# Bpod_Controller.net
KiCad netlist of a schematic drawn in Altium Designer
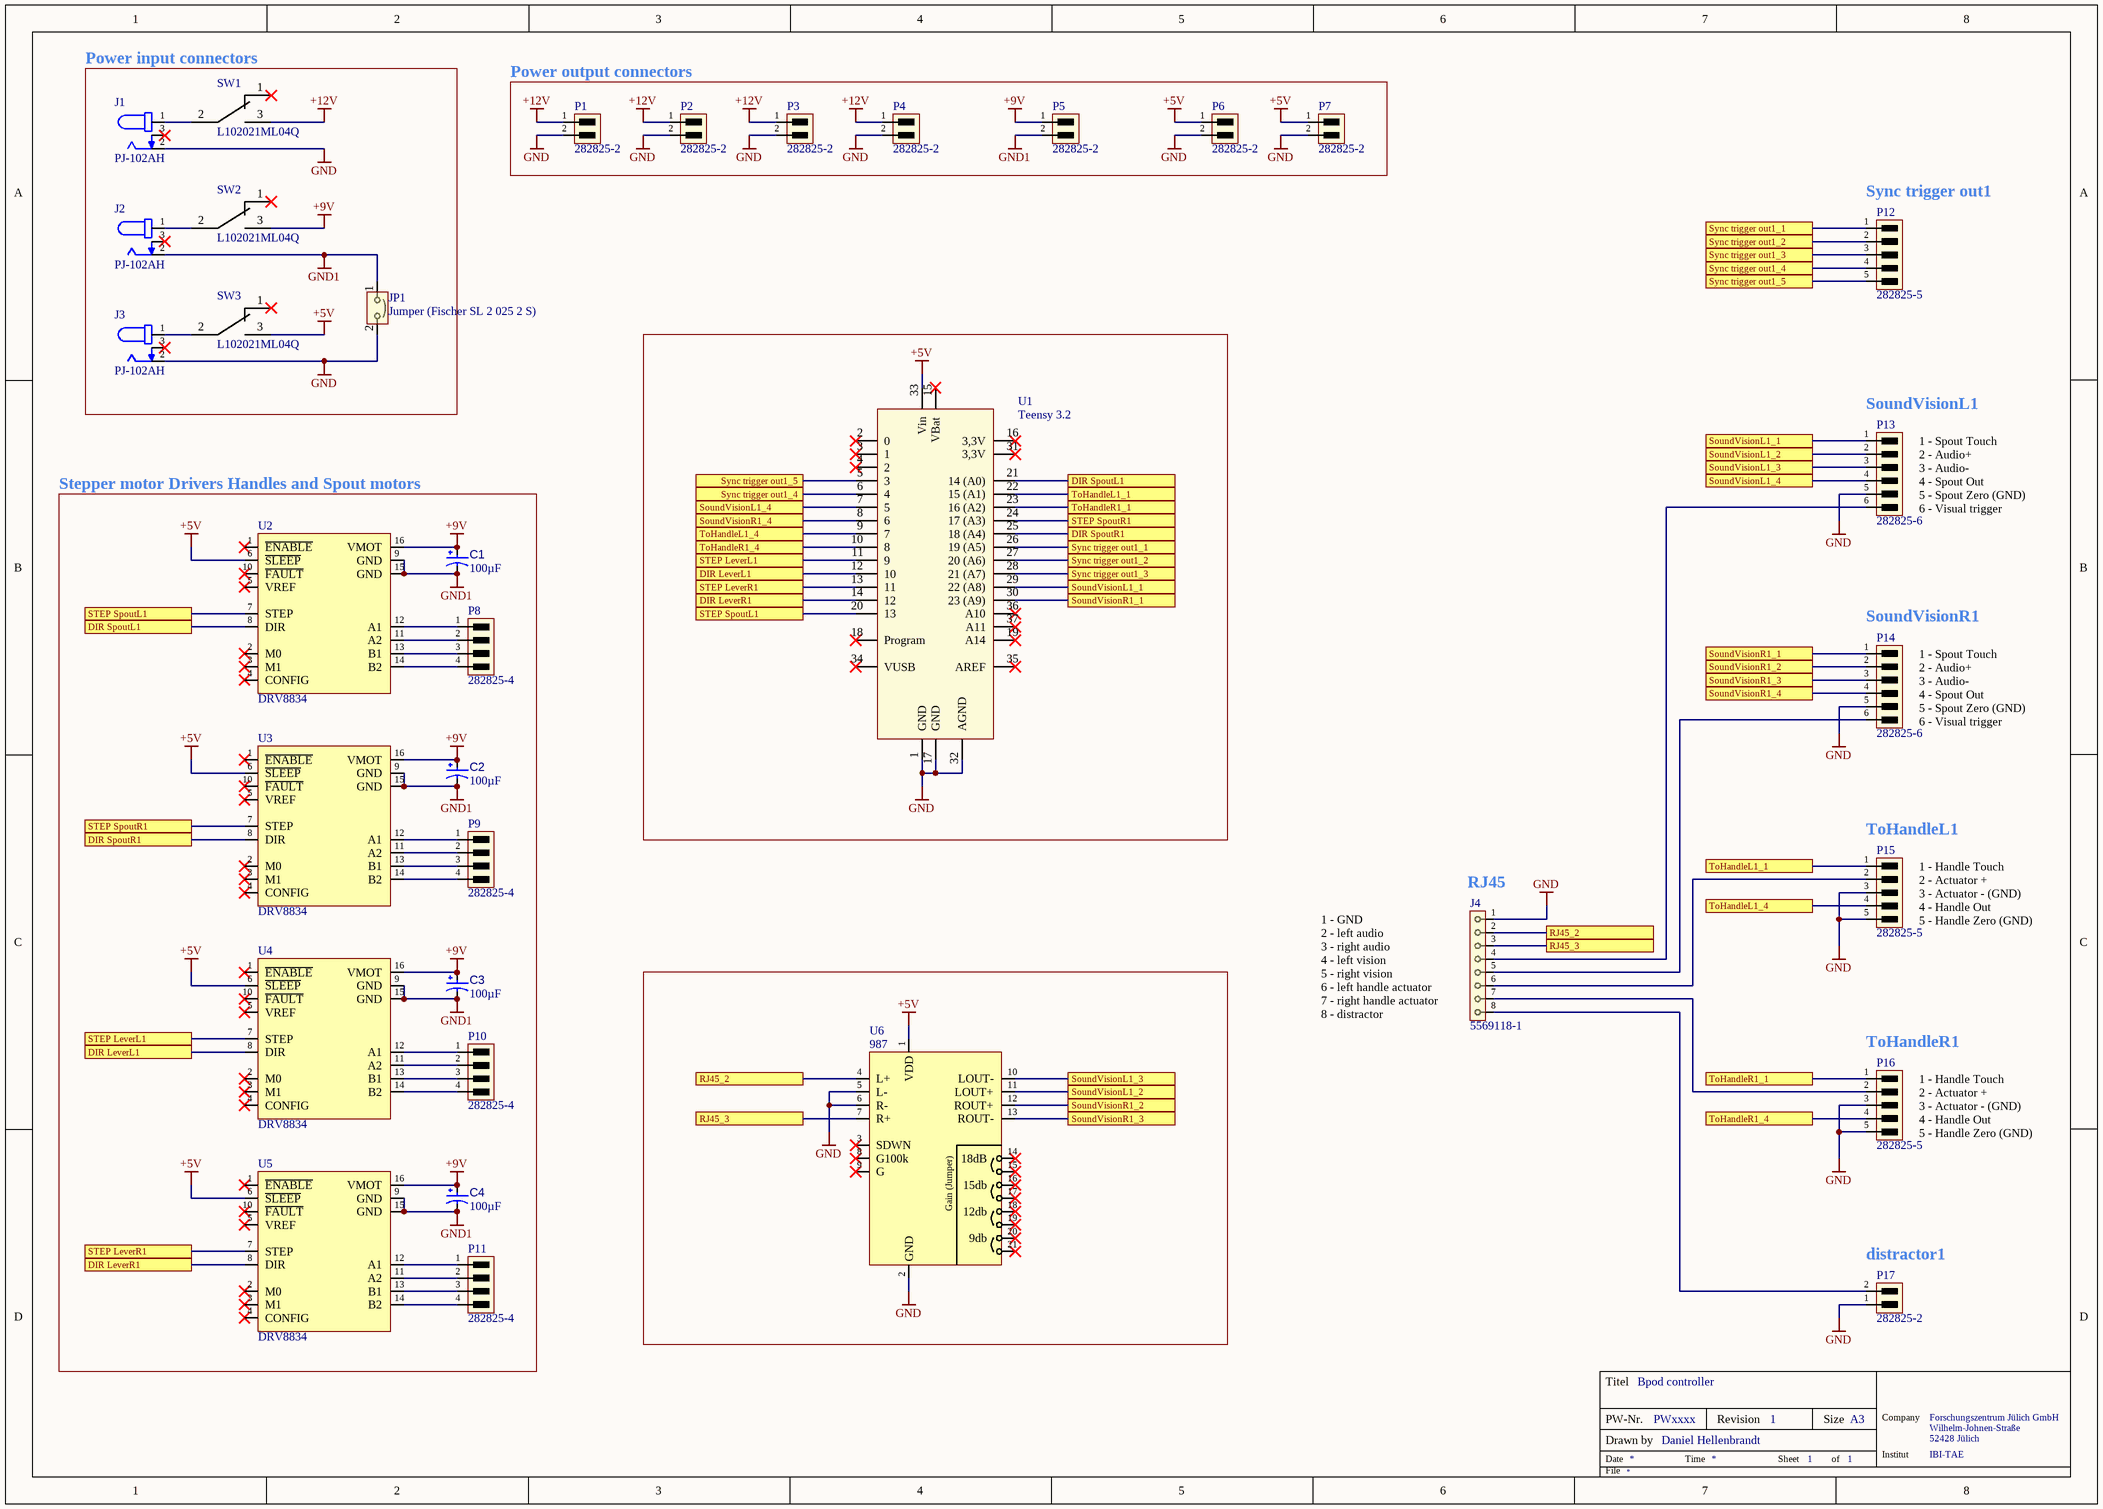
[diagram p0: Bpod Controller.SchDoc]

(export (version "E")
  (design (tool "Eeschema 10.0.6"))
  (components
    (comp (ref "C1")
      (value "100µF")
      (footprint "AVX-TAJ-C-2_M")
      (description "Standard Tantalum, 100 uF, +/- 10%, 16 V, -55 to 125 degC, 2312 (6032 Metric), RoHS, Tape and Reel")
      (fields (field (name "TOLERANCE") "10%") (field (name "MANUFACTURER") "AVX"))
      (libsource (lib "Forschungszentrum Jülich GmbH") (part "CAP-P-2"))
    )
    (comp (ref "C2")
      (value "100µF")
      (footprint "AVX-TAJ-C-2_M")
      (description "Standard Tantalum, 100 uF, +/- 10%, 16 V, -55 to 125 degC, 2312 (6032 Metric), RoHS, Tape and Reel")
      (fields (field (name "TOLERANCE") "10%") (field (name "MANUFACTURER") "AVX"))
      (libsource (lib "Forschungszentrum Jülich GmbH") (part "CAP-P-2"))
    )
    (comp (ref "C3")
      (value "100µF")
      (footprint "AVX-TAJ-C-2_M")
      (description "Standard Tantalum, 100 uF, +/- 10%, 16 V, -55 to 125 degC, 2312 (6032 Metric), RoHS, Tape and Reel")
      (fields (field (name "TOLERANCE") "10%") (field (name "MANUFACTURER") "AVX"))
      (libsource (lib "Forschungszentrum Jülich GmbH") (part "CAP-P-2"))
    )
    (comp (ref "C4")
      (value "100µF")
      (footprint "AVX-TAJ-C-2_M")
      (description "Standard Tantalum, 100 uF, +/- 10%, 16 V, -55 to 125 degC, 2312 (6032 Metric), RoHS, Tape and Reel")
      (fields (field (name "TOLERANCE") "10%") (field (name "MANUFACTURER") "AVX"))
      (libsource (lib "Forschungszentrum Jülich GmbH") (part "CAP-P-2"))
    )
    (comp (ref "J1")
      (value "PJ-102AH")
      (footprint "CUI_PJ-102AH")
      (description "12V, 2.5A, 2mm Dia")
      (fields (field (name "USER") "IBI-TAE"))
      (libsource (lib "Forschungszentrum Jülich GmbH") (part "PJ-102AH"))
    )
    (comp (ref "J2")
      (value "PJ-102AH")
      (footprint "CUI_PJ-102AH")
      (description "12V, 2.5A, 2mm Dia")
      (fields (field (name "USER") "IBI-TAE"))
      (libsource (lib "Forschungszentrum Jülich GmbH") (part "PJ-102AH"))
    )
    (comp (ref "J3")
      (value "PJ-102AH")
      (footprint "CUI_PJ-102AH")
      (description "12V, 2.5A, 2mm Dia")
      (fields (field (name "USER") "IBI-TAE"))
      (libsource (lib "Forschungszentrum Jülich GmbH") (part "PJ-102AH"))
    )
    (comp (ref "J4")
      (value "5569118-1")
      (footprint "5569118-1-Footprint-1")
      (description "Telecom and Datacom Connector, 8 Contact(s), Female, Right Angle, Solder Terminal, Locking, Jack")
      (fields (field (name "USER") "IBI-TAE"))
      (libsource (lib "Forschungszentrum Jülich GmbH") (part "5569118-1"))
    )
    (comp (ref "JP1")
      (value "Jumper (Fischer SL 2 025 2 S)")
      (footprint "SL 2_025_ 72_S-Footprint-1")
      (description "Fischer Elektronik SL 2/025/ 72/S")
      (fields (field (name "USER") "IBI-TAE"))
      (libsource (lib "Forschungszentrum Jülich GmbH") (part "SL 2_025_ 2_S"))
    )
    (comp (ref "P1")
      (value "282825-2")
      (footprint "282825-4-Footprint-1")
      (description "Strip Terminal Block, 15A, 1 Row(s), 1 Deck(s)")
      (fields (field (name "USER") "IBI-TAE"))
      (libsource (lib "Forschungszentrum Jülich GmbH") (part "282825-2"))
    )
    (comp (ref "P2")
      (value "282825-2")
      (footprint "282825-4-Footprint-1")
      (description "Strip Terminal Block, 15A, 1 Row(s), 1 Deck(s)")
      (fields (field (name "USER") "IBI-TAE"))
      (libsource (lib "Forschungszentrum Jülich GmbH") (part "282825-2"))
    )
    (comp (ref "P3")
      (value "282825-2")
      (footprint "282825-4-Footprint-1")
      (description "Strip Terminal Block, 15A, 1 Row(s), 1 Deck(s)")
      (fields (field (name "USER") "IBI-TAE"))
      (libsource (lib "Forschungszentrum Jülich GmbH") (part "282825-2"))
    )
    (comp (ref "P4")
      (value "282825-2")
      (footprint "282825-4-Footprint-1")
      (description "Strip Terminal Block, 15A, 1 Row(s), 1 Deck(s)")
      (fields (field (name "USER") "IBI-TAE"))
      (libsource (lib "Forschungszentrum Jülich GmbH") (part "282825-2"))
    )
    (comp (ref "P5")
      (value "282825-2")
      (footprint "282825-4-Footprint-1")
      (description "Strip Terminal Block, 15A, 1 Row(s), 1 Deck(s)")
      (fields (field (name "USER") "IBI-TAE"))
      (libsource (lib "Forschungszentrum Jülich GmbH") (part "282825-2"))
    )
    (comp (ref "P6")
      (value "282825-2")
      (footprint "282825-4-Footprint-1")
      (description "Strip Terminal Block, 15A, 1 Row(s), 1 Deck(s)")
      (fields (field (name "USER") "IBI-TAE"))
      (libsource (lib "Forschungszentrum Jülich GmbH") (part "282825-2"))
    )
    (comp (ref "P7")
      (value "282825-2")
      (footprint "282825-4-Footprint-1")
      (description "Strip Terminal Block, 15A, 1 Row(s), 1 Deck(s)")
      (fields (field (name "USER") "IBI-TAE"))
      (libsource (lib "Forschungszentrum Jülich GmbH") (part "282825-2"))
    )
    (comp (ref "P8")
      (value "282825-4")
      (footprint "282825-4-Footprint-1")
      (description "Strip Terminal Block, 15A, 1 Row(s), 1 Deck(s)")
      (fields (field (name "USER") "IBI-TAE"))
      (libsource (lib "Forschungszentrum Jülich GmbH") (part "282825-4"))
    )
    (comp (ref "P9")
      (value "282825-4")
      (footprint "282825-4-Footprint-1")
      (description "Strip Terminal Block, 15A, 1 Row(s), 1 Deck(s)")
      (fields (field (name "USER") "IBI-TAE"))
      (libsource (lib "Forschungszentrum Jülich GmbH") (part "282825-4"))
    )
    (comp (ref "P10")
      (value "282825-4")
      (footprint "282825-4-Footprint-1")
      (description "Strip Terminal Block, 15A, 1 Row(s), 1 Deck(s)")
      (fields (field (name "USER") "IBI-TAE"))
      (libsource (lib "Forschungszentrum Jülich GmbH") (part "282825-4"))
    )
    (comp (ref "P11")
      (value "282825-4")
      (footprint "282825-4-Footprint-1")
      (description "Strip Terminal Block, 15A, 1 Row(s), 1 Deck(s)")
      (fields (field (name "USER") "IBI-TAE"))
      (libsource (lib "Forschungszentrum Jülich GmbH") (part "282825-4"))
    )
    (comp (ref "P12")
      (value "282825-5")
      (footprint "282825-4-Footprint-1")
      (description "Strip Terminal Block, 15A, 1 Row(s), 1 Deck(s)")
      (fields (field (name "USER") "IBI-TAE"))
      (libsource (lib "Forschungszentrum Jülich GmbH") (part "282825-5"))
    )
    (comp (ref "P13")
      (value "282825-6")
      (footprint "282825-4-Footprint-1")
      (description "Strip Terminal Block, 15A, 1 Row(s), 1 Deck(s)")
      (fields (field (name "USER") "IBI-TAE"))
      (libsource (lib "Forschungszentrum Jülich GmbH") (part "282825-6"))
    )
    (comp (ref "P14")
      (value "282825-6")
      (footprint "282825-4-Footprint-1")
      (description "Strip Terminal Block, 15A, 1 Row(s), 1 Deck(s)")
      (fields (field (name "USER") "IBI-TAE"))
      (libsource (lib "Forschungszentrum Jülich GmbH") (part "282825-6"))
    )
    (comp (ref "P15")
      (value "282825-5")
      (footprint "282825-4-Footprint-1")
      (description "Strip Terminal Block, 15A, 1 Row(s), 1 Deck(s)")
      (fields (field (name "USER") "IBI-TAE"))
      (libsource (lib "Forschungszentrum Jülich GmbH") (part "282825-5"))
    )
    (comp (ref "P16")
      (value "282825-5")
      (footprint "282825-4-Footprint-1")
      (description "Strip Terminal Block, 15A, 1 Row(s), 1 Deck(s)")
      (fields (field (name "USER") "IBI-TAE"))
      (libsource (lib "Forschungszentrum Jülich GmbH") (part "282825-5"))
    )
    (comp (ref "P17")
      (value "282825-2")
      (footprint "282825-4-Footprint-1")
      (description "Strip Terminal Block, 15A, 1 Row(s), 1 Deck(s)")
      (fields (field (name "USER") "IBI-TAE"))
      (libsource (lib "") (part "282825-2_1"))
    )
    (comp (ref "SW1")
      (value "L102021ML04Q")
      (footprint "L102021ML04Q-Footprint-1")
      (description "Slide Switch, 1 Positions, SPDT, Latched, 4A, 28VDC, Solder Terminal, Through Hole-right Angle")
      (libsource (lib "Forschungszentrum Jülich GmbH") (part "L102021ML04Q-Symbol-1"))
    )
    (comp (ref "SW2")
      (value "L102021ML04Q")
      (footprint "L102021ML04Q-Footprint-1")
      (description "Slide Switch, 1 Positions, SPDT, Latched, 4A, 28VDC, Solder Terminal, Through Hole-right Angle")
      (libsource (lib "Forschungszentrum Jülich GmbH") (part "L102021ML04Q-Symbol-1"))
    )
    (comp (ref "SW3")
      (value "L102021ML04Q")
      (footprint "L102021ML04Q-Footprint-1")
      (description "Slide Switch, 1 Positions, SPDT, Latched, 4A, 28VDC, Solder Terminal, Through Hole-right Angle")
      (libsource (lib "Forschungszentrum Jülich GmbH") (part "L102021ML04Q-Symbol-1"))
    )
    (comp (ref "U1")
      (value "Teensy 3.2")
      (footprint "New footprint 1")
      (description "Development Boards & Kits, ARM Teensy 3.2 and header")
      (fields (field (name "USER") "IBI-TAE"))
      (libsource (lib "Forschungszentrum Jülich GmbH") (part "Teensy 3,2"))
    )
    (comp (ref "U2")
      (value "DRV8834")
      (footprint "DRV8825 STEPPER MOTOR DRIVER CARRIER-Footprint-1")
      (description "DRV8834 Low-Voltage Stepper Motor Driver Carrier")
      (fields (field (name "USER") "IBI-TAE"))
      (libsource (lib "Forschungszentrum Jülich GmbH") (part "Pololu DRV8834"))
    )
    (comp (ref "U3")
      (value "DRV8834")
      (footprint "DRV8825 STEPPER MOTOR DRIVER CARRIER-Footprint-1")
      (description "DRV8834 Low-Voltage Stepper Motor Driver Carrier")
      (fields (field (name "USER") "IBI-TAE"))
      (libsource (lib "Forschungszentrum Jülich GmbH") (part "Pololu DRV8834"))
    )
    (comp (ref "U4")
      (value "DRV8834")
      (footprint "DRV8825 STEPPER MOTOR DRIVER CARRIER-Footprint-1")
      (description "DRV8834 Low-Voltage Stepper Motor Driver Carrier")
      (fields (field (name "USER") "IBI-TAE"))
      (libsource (lib "Forschungszentrum Jülich GmbH") (part "Pololu DRV8834"))
    )
    (comp (ref "U5")
      (value "DRV8834")
      (footprint "DRV8825 STEPPER MOTOR DRIVER CARRIER-Footprint-1")
      (description "DRV8834 Low-Voltage Stepper Motor Driver Carrier")
      (fields (field (name "USER") "IBI-TAE"))
      (libsource (lib "Forschungszentrum Jülich GmbH") (part "Pololu DRV8834"))
    )
    (comp (ref "U6")
      (value "987")
      (footprint "987-Footprint-1")
      (description "Stereo 3.7W Class D Amplifier - Max98306; Product Range: -; Plug Type: - Rohs Compliant: Yes")
      (fields (field (name "USER") "IBI-TAE"))
      (libsource (lib "Forschungszentrum Jülich GmbH") (part "987"))
    )
  )
  (nets
    (net (code "1") (name "+5V") (class "Default")
      (node (ref "P6") (pin "1") (pinfunction "1_1") (pintype "passive"))
      (node (ref "P7") (pin "1") (pinfunction "1_1") (pintype "passive"))
      (node (ref "SW3") (pin "3") (pinfunction "3_3") (pintype "passive"))
      (node (ref "U1") (pin "33") (pinfunction "Vin_33") (pintype "power_in"))
      (node (ref "U2") (pin "6") (pinfunction "~{SLEEP}_6") (pintype "passive"))
      (node (ref "U3") (pin "6") (pinfunction "~{SLEEP}_6") (pintype "passive"))
      (node (ref "U4") (pin "6") (pinfunction "~{SLEEP}_6") (pintype "passive"))
      (node (ref "U5") (pin "6") (pinfunction "~{SLEEP}_6") (pintype "passive"))
      (node (ref "U6") (pin "1") (pinfunction "VDD_1") (pintype "passive"))
    )
    (net (code "2") (name "+9V") (class "Default")
      (node (ref "C1") (pin "1") (pinfunction "1_1") (pintype "passive"))
      (node (ref "C2") (pin "1") (pinfunction "1_1") (pintype "passive"))
      (node (ref "C3") (pin "1") (pinfunction "1_1") (pintype "passive"))
      (node (ref "C4") (pin "1") (pinfunction "1_1") (pintype "passive"))
      (node (ref "P5") (pin "1") (pinfunction "1_1") (pintype "passive"))
      (node (ref "SW2") (pin "3") (pinfunction "3_3") (pintype "passive"))
      (node (ref "U2") (pin "16") (pinfunction "VMOT_16") (pintype "passive"))
      (node (ref "U3") (pin "16") (pinfunction "VMOT_16") (pintype "passive"))
      (node (ref "U4") (pin "16") (pinfunction "VMOT_16") (pintype "passive"))
      (node (ref "U5") (pin "16") (pinfunction "VMOT_16") (pintype "passive"))
    )
    (net (code "3") (name "+12V") (class "Default")
      (node (ref "P1") (pin "1") (pinfunction "1_1") (pintype "passive"))
      (node (ref "P2") (pin "1") (pinfunction "1_1") (pintype "passive"))
      (node (ref "P3") (pin "1") (pinfunction "1_1") (pintype "passive"))
      (node (ref "P4") (pin "1") (pinfunction "1_1") (pintype "passive"))
      (node (ref "SW1") (pin "3") (pinfunction "3_3") (pintype "passive"))
    )
    (net (code "4") (name "/DIR LeverL1") (class "Default")
      (node (ref "U1") (pin "12") (pinfunction "10_12") (pintype "passive"))
      (node (ref "U4") (pin "8") (pinfunction "DIR_8") (pintype "passive"))
    )
    (net (code "5") (name "/DIR LeverR1") (class "Default")
      (node (ref "U1") (pin "14") (pinfunction "12_14") (pintype "passive"))
      (node (ref "U5") (pin "8") (pinfunction "DIR_8") (pintype "passive"))
    )
    (net (code "6") (name "/DIR SpoutL1") (class "Default")
      (node (ref "U1") (pin "21") (pinfunction "14_(A0)_21") (pintype "passive"))
      (node (ref "U2") (pin "8") (pinfunction "DIR_8") (pintype "passive"))
    )
    (net (code "7") (name "/DIR SpoutR1") (class "Default")
      (node (ref "U1") (pin "25") (pinfunction "18_(A4)_25") (pintype "passive"))
      (node (ref "U3") (pin "8") (pinfunction "DIR_8") (pintype "passive"))
    )
    (net (code "8") (name "/RJ45_2") (class "Default")
      (node (ref "J4") (pin "2") (pinfunction "2_2") (pintype "passive"))
      (node (ref "U6") (pin "4") (pinfunction "L+_4") (pintype "passive"))
    )
    (net (code "9") (name "/RJ45_3") (class "Default")
      (node (ref "J4") (pin "3") (pinfunction "3_3") (pintype "passive"))
      (node (ref "U6") (pin "7") (pinfunction "R+_7") (pintype "passive"))
    )
    (net (code "10") (name "/STEP LeverL1") (class "Default")
      (node (ref "U1") (pin "11") (pinfunction "9_11") (pintype "passive"))
      (node (ref "U4") (pin "7") (pinfunction "STEP_7") (pintype "passive"))
    )
    (net (code "11") (name "/STEP LeverR1") (class "Default")
      (node (ref "U1") (pin "13") (pinfunction "11_13") (pintype "passive"))
      (node (ref "U5") (pin "7") (pinfunction "STEP_7") (pintype "passive"))
    )
    (net (code "12") (name "/STEP SpoutL1") (class "Default")
      (node (ref "U1") (pin "20") (pinfunction "13_20") (pintype "passive"))
      (node (ref "U2") (pin "7") (pinfunction "STEP_7") (pintype "passive"))
    )
    (net (code "13") (name "/STEP SpoutR1") (class "Default")
      (node (ref "U1") (pin "24") (pinfunction "17_(A3)_24") (pintype "passive"))
      (node (ref "U3") (pin "7") (pinfunction "STEP_7") (pintype "passive"))
    )
    (net (code "14") (name "/SoundVisionL1_1") (class "Default")
      (node (ref "P13") (pin "1") (pinfunction "1_1") (pintype "passive"))
      (node (ref "U1") (pin "29") (pinfunction "22_(A8)_29") (pintype "passive"))
    )
    (net (code "15") (name "/SoundVisionL1_2") (class "Default")
      (node (ref "P13") (pin "2") (pinfunction "2_2") (pintype "passive"))
      (node (ref "U6") (pin "11") (pinfunction "LOUT+_11") (pintype "passive"))
    )
    (net (code "16") (name "/SoundVisionL1_3") (class "Default")
      (node (ref "P13") (pin "3") (pinfunction "3_3") (pintype "passive"))
      (node (ref "U6") (pin "10") (pinfunction "LOUT-_10") (pintype "passive"))
    )
    (net (code "17") (name "/SoundVisionL1_4") (class "Default")
      (node (ref "P13") (pin "4") (pinfunction "4_4") (pintype "passive"))
      (node (ref "U1") (pin "7") (pinfunction "5_7") (pintype "passive"))
    )
    (net (code "18") (name "/SoundVisionR1_1") (class "Default")
      (node (ref "P14") (pin "1") (pinfunction "1_1") (pintype "passive"))
      (node (ref "U1") (pin "30") (pinfunction "23_(A9)_30") (pintype "passive"))
    )
    (net (code "19") (name "/SoundVisionR1_2") (class "Default")
      (node (ref "P14") (pin "2") (pinfunction "2_2") (pintype "passive"))
      (node (ref "U6") (pin "12") (pinfunction "ROUT+_12") (pintype "passive"))
    )
    (net (code "20") (name "/SoundVisionR1_3") (class "Default")
      (node (ref "P14") (pin "3") (pinfunction "3_3") (pintype "passive"))
      (node (ref "U6") (pin "13") (pinfunction "ROUT-_13") (pintype "passive"))
    )
    (net (code "21") (name "/SoundVisionR1_4") (class "Default")
      (node (ref "P14") (pin "4") (pinfunction "4_4") (pintype "passive"))
      (node (ref "U1") (pin "8") (pinfunction "6_8") (pintype "passive"))
    )
    (net (code "22") (name "/Sync trigger out1_1") (class "Default")
      (node (ref "P12") (pin "1") (pinfunction "1_1") (pintype "passive"))
      (node (ref "U1") (pin "26") (pinfunction "19_(A5)_26") (pintype "passive"))
    )
    (net (code "23") (name "/Sync trigger out1_2") (class "Default")
      (node (ref "P12") (pin "2") (pinfunction "2_2") (pintype "passive"))
      (node (ref "U1") (pin "27") (pinfunction "20_(A6)_27") (pintype "passive"))
    )
    (net (code "24") (name "/Sync trigger out1_3") (class "Default")
      (node (ref "P12") (pin "3") (pinfunction "3_3") (pintype "passive"))
      (node (ref "U1") (pin "28") (pinfunction "21_(A7)_28") (pintype "passive"))
    )
    (net (code "25") (name "/Sync trigger out1_4") (class "Default")
      (node (ref "P12") (pin "4") (pinfunction "4_4") (pintype "passive"))
      (node (ref "U1") (pin "6") (pinfunction "4_6") (pintype "passive"))
    )
    (net (code "26") (name "/Sync trigger out1_5") (class "Default")
      (node (ref "P12") (pin "5") (pinfunction "5_5") (pintype "passive"))
      (node (ref "U1") (pin "5") (pinfunction "3_5") (pintype "passive"))
    )
    (net (code "27") (name "/ToHandleL1_1") (class "Default")
      (node (ref "P15") (pin "1") (pinfunction "1_1") (pintype "passive"))
      (node (ref "U1") (pin "22") (pinfunction "15_(A1)_22") (pintype "passive"))
    )
    (net (code "28") (name "/ToHandleL1_4") (class "Default")
      (node (ref "P15") (pin "4") (pinfunction "4_4") (pintype "passive"))
      (node (ref "U1") (pin "9") (pinfunction "7_9") (pintype "passive"))
    )
    (net (code "29") (name "/ToHandleR1_1") (class "Default")
      (node (ref "P16") (pin "1") (pinfunction "1_1") (pintype "passive"))
      (node (ref "U1") (pin "23") (pinfunction "16_(A2)_23") (pintype "passive"))
    )
    (net (code "30") (name "/ToHandleR1_4") (class "Default")
      (node (ref "P16") (pin "4") (pinfunction "4_4") (pintype "passive"))
      (node (ref "U1") (pin "10") (pinfunction "8_10") (pintype "passive"))
    )
    (net (code "31") (name "GND") (class "Default")
      (node (ref "J1") (pin "2") (pinfunction "2_2") (pintype "passive"))
      (node (ref "J3") (pin "2") (pinfunction "2_2") (pintype "passive"))
      (node (ref "J4") (pin "1") (pinfunction "1_1") (pintype "passive"))
      (node (ref "JP1") (pin "2") (pinfunction "2_2") (pintype "passive"))
      (node (ref "P1") (pin "2") (pinfunction "2_2") (pintype "passive"))
      (node (ref "P13") (pin "5") (pinfunction "5_5") (pintype "passive"))
      (node (ref "P14") (pin "5") (pinfunction "5_5") (pintype "passive"))
      (node (ref "P15") (pin "3") (pinfunction "3_3") (pintype "passive"))
      (node (ref "P15") (pin "5") (pinfunction "5_5") (pintype "passive"))
      (node (ref "P16") (pin "3") (pinfunction "3_3") (pintype "passive"))
      (node (ref "P16") (pin "5") (pinfunction "5_5") (pintype "passive"))
      (node (ref "P17") (pin "1") (pinfunction "1_1") (pintype "passive"))
      (node (ref "P2") (pin "2") (pinfunction "2_2") (pintype "passive"))
      (node (ref "P3") (pin "2") (pinfunction "2_2") (pintype "passive"))
      (node (ref "P4") (pin "2") (pinfunction "2_2") (pintype "passive"))
      (node (ref "P6") (pin "2") (pinfunction "2_2") (pintype "passive"))
      (node (ref "P7") (pin "2") (pinfunction "2_2") (pintype "passive"))
      (node (ref "U1") (pin "1") (pinfunction "GND_1") (pintype "passive"))
      (node (ref "U1") (pin "17") (pinfunction "GND_17") (pintype "passive"))
      (node (ref "U1") (pin "32") (pinfunction "AGND_32") (pintype "passive"))
      (node (ref "U6") (pin "2") (pinfunction "GND_2") (pintype "passive"))
      (node (ref "U6") (pin "5") (pinfunction "L-_5") (pintype "passive"))
      (node (ref "U6") (pin "6") (pinfunction "R-_6") (pintype "passive"))
    )
    (net (code "32") (name "GND1") (class "Default")
      (node (ref "C1") (pin "2") (pinfunction "2_2") (pintype "passive"))
      (node (ref "C2") (pin "2") (pinfunction "2_2") (pintype "passive"))
      (node (ref "C3") (pin "2") (pinfunction "2_2") (pintype "passive"))
      (node (ref "C4") (pin "2") (pinfunction "2_2") (pintype "passive"))
      (node (ref "J2") (pin "2") (pinfunction "2_2") (pintype "passive"))
      (node (ref "JP1") (pin "1") (pinfunction "1_1") (pintype "passive"))
      (node (ref "P5") (pin "2") (pinfunction "2_2") (pintype "passive"))
      (node (ref "U2") (pin "15") (pinfunction "GND_15") (pintype "passive"))
      (node (ref "U2") (pin "9") (pinfunction "GND_9") (pintype "passive"))
      (node (ref "U3") (pin "15") (pinfunction "GND_15") (pintype "passive"))
      (node (ref "U3") (pin "9") (pinfunction "GND_9") (pintype "passive"))
      (node (ref "U4") (pin "15") (pinfunction "GND_15") (pintype "passive"))
      (node (ref "U4") (pin "9") (pinfunction "GND_9") (pintype "passive"))
      (node (ref "U5") (pin "15") (pinfunction "GND_15") (pintype "passive"))
      (node (ref "U5") (pin "9") (pinfunction "GND_9") (pintype "passive"))
    )
    (net (code "33") (name "Net-(J1-Pad1)") (class "Default")
      (node (ref "J1") (pin "1") (pinfunction "1_1") (pintype "passive"))
      (node (ref "SW1") (pin "2") (pinfunction "2_2") (pintype "passive"))
    )
    (net (code "34") (name "Net-(J2-Pad1)") (class "Default")
      (node (ref "J2") (pin "1") (pinfunction "1_1") (pintype "passive"))
      (node (ref "SW2") (pin "2") (pinfunction "2_2") (pintype "passive"))
    )
    (net (code "35") (name "Net-(J3-Pad1)") (class "Default")
      (node (ref "J3") (pin "1") (pinfunction "1_1") (pintype "passive"))
      (node (ref "SW3") (pin "2") (pinfunction "2_2") (pintype "passive"))
    )
    (net (code "36") (name "Net-(J4-Pad4)") (class "Default")
      (node (ref "J4") (pin "4") (pinfunction "4_4") (pintype "passive"))
      (node (ref "P13") (pin "6") (pinfunction "6_6") (pintype "passive"))
    )
    (net (code "37") (name "Net-(J4-Pad5)") (class "Default")
      (node (ref "J4") (pin "5") (pinfunction "5_5") (pintype "passive"))
      (node (ref "P14") (pin "6") (pinfunction "6_6") (pintype "passive"))
    )
    (net (code "38") (name "Net-(J4-Pad6)") (class "Default")
      (node (ref "J4") (pin "6") (pinfunction "6_6") (pintype "passive"))
      (node (ref "P15") (pin "2") (pinfunction "2_2") (pintype "passive"))
    )
    (net (code "39") (name "Net-(J4-Pad7)") (class "Default")
      (node (ref "J4") (pin "7") (pinfunction "7_7") (pintype "passive"))
      (node (ref "P16") (pin "2") (pinfunction "2_2") (pintype "passive"))
    )
    (net (code "40") (name "Net-(J4-Pad8)") (class "Default")
      (node (ref "J4") (pin "8") (pinfunction "8_8") (pintype "passive"))
      (node (ref "P17") (pin "2") (pinfunction "2_2") (pintype "passive"))
    )
    (net (code "41") (name "Net-(U2-A1)") (class "Default")
      (node (ref "P8") (pin "1") (pinfunction "1_1") (pintype "passive"))
      (node (ref "U2") (pin "12") (pinfunction "A1_12") (pintype "passive"))
    )
    (net (code "42") (name "Net-(U2-A2)") (class "Default")
      (node (ref "P8") (pin "2") (pinfunction "2_2") (pintype "passive"))
      (node (ref "U2") (pin "11") (pinfunction "A2_11") (pintype "passive"))
    )
    (net (code "43") (name "Net-(U2-B1)") (class "Default")
      (node (ref "P8") (pin "3") (pinfunction "3_3") (pintype "passive"))
      (node (ref "U2") (pin "13") (pinfunction "B1_13") (pintype "passive"))
    )
    (net (code "44") (name "Net-(U2-B2)") (class "Default")
      (node (ref "P8") (pin "4") (pinfunction "4_4") (pintype "passive"))
      (node (ref "U2") (pin "14") (pinfunction "B2_14") (pintype "passive"))
    )
    (net (code "45") (name "Net-(U3-A1)") (class "Default")
      (node (ref "P9") (pin "1") (pinfunction "1_1") (pintype "passive"))
      (node (ref "U3") (pin "12") (pinfunction "A1_12") (pintype "passive"))
    )
    (net (code "46") (name "Net-(U3-A2)") (class "Default")
      (node (ref "P9") (pin "2") (pinfunction "2_2") (pintype "passive"))
      (node (ref "U3") (pin "11") (pinfunction "A2_11") (pintype "passive"))
    )
    (net (code "47") (name "Net-(U3-B1)") (class "Default")
      (node (ref "P9") (pin "3") (pinfunction "3_3") (pintype "passive"))
      (node (ref "U3") (pin "13") (pinfunction "B1_13") (pintype "passive"))
    )
    (net (code "48") (name "Net-(U3-B2)") (class "Default")
      (node (ref "P9") (pin "4") (pinfunction "4_4") (pintype "passive"))
      (node (ref "U3") (pin "14") (pinfunction "B2_14") (pintype "passive"))
    )
    (net (code "49") (name "Net-(U4-A1)") (class "Default")
      (node (ref "P10") (pin "1") (pinfunction "1_1") (pintype "passive"))
      (node (ref "U4") (pin "12") (pinfunction "A1_12") (pintype "passive"))
    )
    (net (code "50") (name "Net-(U4-A2)") (class "Default")
      (node (ref "P10") (pin "2") (pinfunction "2_2") (pintype "passive"))
      (node (ref "U4") (pin "11") (pinfunction "A2_11") (pintype "passive"))
    )
    (net (code "51") (name "Net-(U4-B1)") (class "Default")
      (node (ref "P10") (pin "3") (pinfunction "3_3") (pintype "passive"))
      (node (ref "U4") (pin "13") (pinfunction "B1_13") (pintype "passive"))
    )
    (net (code "52") (name "Net-(U4-B2)") (class "Default")
      (node (ref "P10") (pin "4") (pinfunction "4_4") (pintype "passive"))
      (node (ref "U4") (pin "14") (pinfunction "B2_14") (pintype "passive"))
    )
    (net (code "53") (name "Net-(U5-A1)") (class "Default")
      (node (ref "P11") (pin "1") (pinfunction "1_1") (pintype "passive"))
      (node (ref "U5") (pin "12") (pinfunction "A1_12") (pintype "passive"))
    )
    (net (code "54") (name "Net-(U5-A2)") (class "Default")
      (node (ref "P11") (pin "2") (pinfunction "2_2") (pintype "passive"))
      (node (ref "U5") (pin "11") (pinfunction "A2_11") (pintype "passive"))
    )
    (net (code "55") (name "Net-(U5-B1)") (class "Default")
      (node (ref "P11") (pin "3") (pinfunction "3_3") (pintype "passive"))
      (node (ref "U5") (pin "13") (pinfunction "B1_13") (pintype "passive"))
    )
    (net (code "56") (name "Net-(U5-B2)") (class "Default")
      (node (ref "P11") (pin "4") (pinfunction "4_4") (pintype "passive"))
      (node (ref "U5") (pin "14") (pinfunction "B2_14") (pintype "passive"))
    )
    (net (code "57") (name "unconnected-(J1-Pad3)") (class "Default")
      (node (ref "J1") (pin "3") (pinfunction "3_3") (pintype "passive"))
    )
    (net (code "58") (name "unconnected-(J2-Pad3)") (class "Default")
      (node (ref "J2") (pin "3") (pinfunction "3_3") (pintype "passive+no_connect"))
    )
    (net (code "59") (name "unconnected-(J3-Pad3)") (class "Default")
      (node (ref "J3") (pin "3") (pinfunction "3_3") (pintype "passive+no_connect"))
    )
    (net (code "60") (name "unconnected-(SW1-Pad1)") (class "Default")
      (node (ref "SW1") (pin "1") (pinfunction "1_1") (pintype "passive+no_connect"))
    )
    (net (code "61") (name "unconnected-(SW2-Pad1)") (class "Default")
      (node (ref "SW2") (pin "1") (pinfunction "1_1") (pintype "passive+no_connect"))
    )
    (net (code "62") (name "unconnected-(SW3-Pad1)") (class "Default")
      (node (ref "SW3") (pin "1") (pinfunction "1_1") (pintype "passive+no_connect"))
    )
    (net (code "63") (name "unconnected-(U1-0-Pad2)") (class "Default")
      (node (ref "U1") (pin "2") (pinfunction "0_2") (pintype "passive+no_connect"))
    )
    (net (code "64") (name "unconnected-(U1-1-Pad3)") (class "Default")
      (node (ref "U1") (pin "3") (pinfunction "1_3") (pintype "passive+no_connect"))
    )
    (net (code "65") (name "unconnected-(U1-2-Pad4)") (class "Default")
      (node (ref "U1") (pin "4") (pinfunction "2_4") (pintype "passive+no_connect"))
    )
    (net (code "66") (name "unconnected-(U1-3,3V-Pad16)") (class "Default")
      (node (ref "U1") (pin "16") (pinfunction "3,3V_16") (pintype "passive+no_connect"))
    )
    (net (code "67") (name "unconnected-(U1-3,3V-Pad31)") (class "Default")
      (node (ref "U1") (pin "31") (pinfunction "3,3V_31") (pintype "passive+no_connect"))
    )
    (net (code "68") (name "unconnected-(U1-A10-Pad36)") (class "Default")
      (node (ref "U1") (pin "36") (pinfunction "A10_36") (pintype "passive+no_connect"))
    )
    (net (code "69") (name "unconnected-(U1-A11-Pad37)") (class "Default")
      (node (ref "U1") (pin "37") (pinfunction "A11_37") (pintype "passive+no_connect"))
    )
    (net (code "70") (name "unconnected-(U1-A14-Pad19)") (class "Default")
      (node (ref "U1") (pin "19") (pinfunction "A14_19") (pintype "passive+no_connect"))
    )
    (net (code "71") (name "unconnected-(U1-AREF-Pad35)") (class "Default")
      (node (ref "U1") (pin "35") (pinfunction "AREF_35") (pintype "passive+no_connect"))
    )
    (net (code "72") (name "unconnected-(U1-Program-Pad18)") (class "Default")
      (node (ref "U1") (pin "18") (pinfunction "Program_18") (pintype "passive+no_connect"))
    )
    (net (code "73") (name "unconnected-(U1-VBat-Pad15)") (class "Default")
      (node (ref "U1") (pin "15") (pinfunction "VBat_15") (pintype "passive+no_connect"))
    )
    (net (code "74") (name "unconnected-(U1-VUSB-Pad34)") (class "Default")
      (node (ref "U1") (pin "34") (pinfunction "VUSB_34") (pintype "passive+no_connect"))
    )
    (net (code "75") (name "unconnected-(U2-CONFIG-Pad4)") (class "Default")
      (node (ref "U2") (pin "4") (pinfunction "CONFIG_4") (pintype "passive+no_connect"))
    )
    (net (code "76") (name "unconnected-(U2-M0-Pad2)") (class "Default")
      (node (ref "U2") (pin "2") (pinfunction "M0_2") (pintype "passive+no_connect"))
    )
    (net (code "77") (name "unconnected-(U2-M1-Pad3)") (class "Default")
      (node (ref "U2") (pin "3") (pinfunction "M1_3") (pintype "passive+no_connect"))
    )
    (net (code "78") (name "unconnected-(U2-VREF-Pad5)") (class "Default")
      (node (ref "U2") (pin "5") (pinfunction "VREF_5") (pintype "passive+no_connect"))
    )
    (net (code "79") (name "unconnected-(U2-~{ENABLE}-Pad1)") (class "Default")
      (node (ref "U2") (pin "1") (pinfunction "~{ENABLE}_1") (pintype "passive+no_connect"))
    )
    (net (code "80") (name "unconnected-(U2-~{FAULT}-Pad10)") (class "Default")
      (node (ref "U2") (pin "10") (pinfunction "~{FAULT}_10") (pintype "passive+no_connect"))
    )
    (net (code "81") (name "unconnected-(U3-CONFIG-Pad4)") (class "Default")
      (node (ref "U3") (pin "4") (pinfunction "CONFIG_4") (pintype "passive+no_connect"))
    )
    (net (code "82") (name "unconnected-(U3-M0-Pad2)") (class "Default")
      (node (ref "U3") (pin "2") (pinfunction "M0_2") (pintype "passive+no_connect"))
    )
    (net (code "83") (name "unconnected-(U3-M1-Pad3)") (class "Default")
      (node (ref "U3") (pin "3") (pinfunction "M1_3") (pintype "passive+no_connect"))
    )
    (net (code "84") (name "unconnected-(U3-VREF-Pad5)") (class "Default")
      (node (ref "U3") (pin "5") (pinfunction "VREF_5") (pintype "passive+no_connect"))
    )
    (net (code "85") (name "unconnected-(U3-~{ENABLE}-Pad1)") (class "Default")
      (node (ref "U3") (pin "1") (pinfunction "~{ENABLE}_1") (pintype "passive+no_connect"))
    )
    (net (code "86") (name "unconnected-(U3-~{FAULT}-Pad10)") (class "Default")
      (node (ref "U3") (pin "10") (pinfunction "~{FAULT}_10") (pintype "passive+no_connect"))
    )
    (net (code "87") (name "unconnected-(U4-CONFIG-Pad4)") (class "Default")
      (node (ref "U4") (pin "4") (pinfunction "CONFIG_4") (pintype "passive+no_connect"))
    )
    (net (code "88") (name "unconnected-(U4-M0-Pad2)") (class "Default")
      (node (ref "U4") (pin "2") (pinfunction "M0_2") (pintype "passive+no_connect"))
    )
    (net (code "89") (name "unconnected-(U4-M1-Pad3)") (class "Default")
      (node (ref "U4") (pin "3") (pinfunction "M1_3") (pintype "passive+no_connect"))
    )
    (net (code "90") (name "unconnected-(U4-VREF-Pad5)") (class "Default")
      (node (ref "U4") (pin "5") (pinfunction "VREF_5") (pintype "passive+no_connect"))
    )
    (net (code "91") (name "unconnected-(U4-~{ENABLE}-Pad1)") (class "Default")
      (node (ref "U4") (pin "1") (pinfunction "~{ENABLE}_1") (pintype "passive+no_connect"))
    )
    (net (code "92") (name "unconnected-(U4-~{FAULT}-Pad10)") (class "Default")
      (node (ref "U4") (pin "10") (pinfunction "~{FAULT}_10") (pintype "passive+no_connect"))
    )
    (net (code "93") (name "unconnected-(U5-CONFIG-Pad4)") (class "Default")
      (node (ref "U5") (pin "4") (pinfunction "CONFIG_4") (pintype "passive+no_connect"))
    )
    (net (code "94") (name "unconnected-(U5-M0-Pad2)") (class "Default")
      (node (ref "U5") (pin "2") (pinfunction "M0_2") (pintype "passive+no_connect"))
    )
    (net (code "95") (name "unconnected-(U5-M1-Pad3)") (class "Default")
      (node (ref "U5") (pin "3") (pinfunction "M1_3") (pintype "passive+no_connect"))
    )
    (net (code "96") (name "unconnected-(U5-VREF-Pad5)") (class "Default")
      (node (ref "U5") (pin "5") (pinfunction "VREF_5") (pintype "passive+no_connect"))
    )
    (net (code "97") (name "unconnected-(U5-~{ENABLE}-Pad1)") (class "Default")
      (node (ref "U5") (pin "1") (pinfunction "~{ENABLE}_1") (pintype "passive+no_connect"))
    )
    (net (code "98") (name "unconnected-(U5-~{FAULT}-Pad10)") (class "Default")
      (node (ref "U5") (pin "10") (pinfunction "~{FAULT}_10") (pintype "passive+no_connect"))
    )
    (net (code "99") (name "unconnected-(U6-9db-Pad20)") (class "Default")
      (node (ref "U6") (pin "20") (pinfunction "9db_20") (pintype "passive+no_connect"))
    )
    (net (code "100") (name "unconnected-(U6-12db-Pad18)") (class "Default")
      (node (ref "U6") (pin "18") (pinfunction "12db_18") (pintype "passive+no_connect"))
    )
    (net (code "101") (name "unconnected-(U6-15db-Pad16)") (class "Default")
      (node (ref "U6") (pin "16") (pinfunction "15db_16") (pintype "passive+no_connect"))
    )
    (net (code "102") (name "unconnected-(U6-18dB-Pad14)") (class "Default")
      (node (ref "U6") (pin "14") (pinfunction "18dB_14") (pintype "passive+no_connect"))
    )
    (net (code "103") (name "unconnected-(U6-G-Pad9)") (class "Default")
      (node (ref "U6") (pin "9") (pinfunction "G_9") (pintype "passive+no_connect"))
    )
    (net (code "104") (name "unconnected-(U6-G100k-Pad8)") (class "Default")
      (node (ref "U6") (pin "8") (pinfunction "G100k_8") (pintype "passive+no_connect"))
    )
    (net (code "105") (name "unconnected-(U6-Pad15)") (class "Default")
      (node (ref "U6") (pin "15") (pinfunction "15_15") (pintype "passive+no_connect"))
    )
    (net (code "106") (name "unconnected-(U6-Pad17)") (class "Default")
      (node (ref "U6") (pin "17") (pinfunction "17_17") (pintype "passive+no_connect"))
    )
    (net (code "107") (name "unconnected-(U6-Pad19)") (class "Default")
      (node (ref "U6") (pin "19") (pinfunction "19_19") (pintype "passive+no_connect"))
    )
    (net (code "108") (name "unconnected-(U6-Pad21)") (class "Default")
      (node (ref "U6") (pin "21") (pinfunction "21_21") (pintype "passive+no_connect"))
    )
    (net (code "109") (name "unconnected-(U6-SDWN-Pad3)") (class "Default")
      (node (ref "U6") (pin "3") (pinfunction "SDWN_3") (pintype "passive+no_connect"))
    )
    (net (code "110") (name "unconnected-(U6-X-Pad22)") (class "Default")
      (node (ref "U6") (pin "22") (pinfunction "X_22") (pintype "passive"))
    )
    (net (code "111") (name "unconnected-(U6-Y-Pad23)") (class "Default")
      (node (ref "U6") (pin "23") (pinfunction "Y_23") (pintype "passive"))
    )
  )
)
